# Adafruit_AHT20_Temperature_Humidity.net
KiCad netlist of a schematic drawn in EAGLE
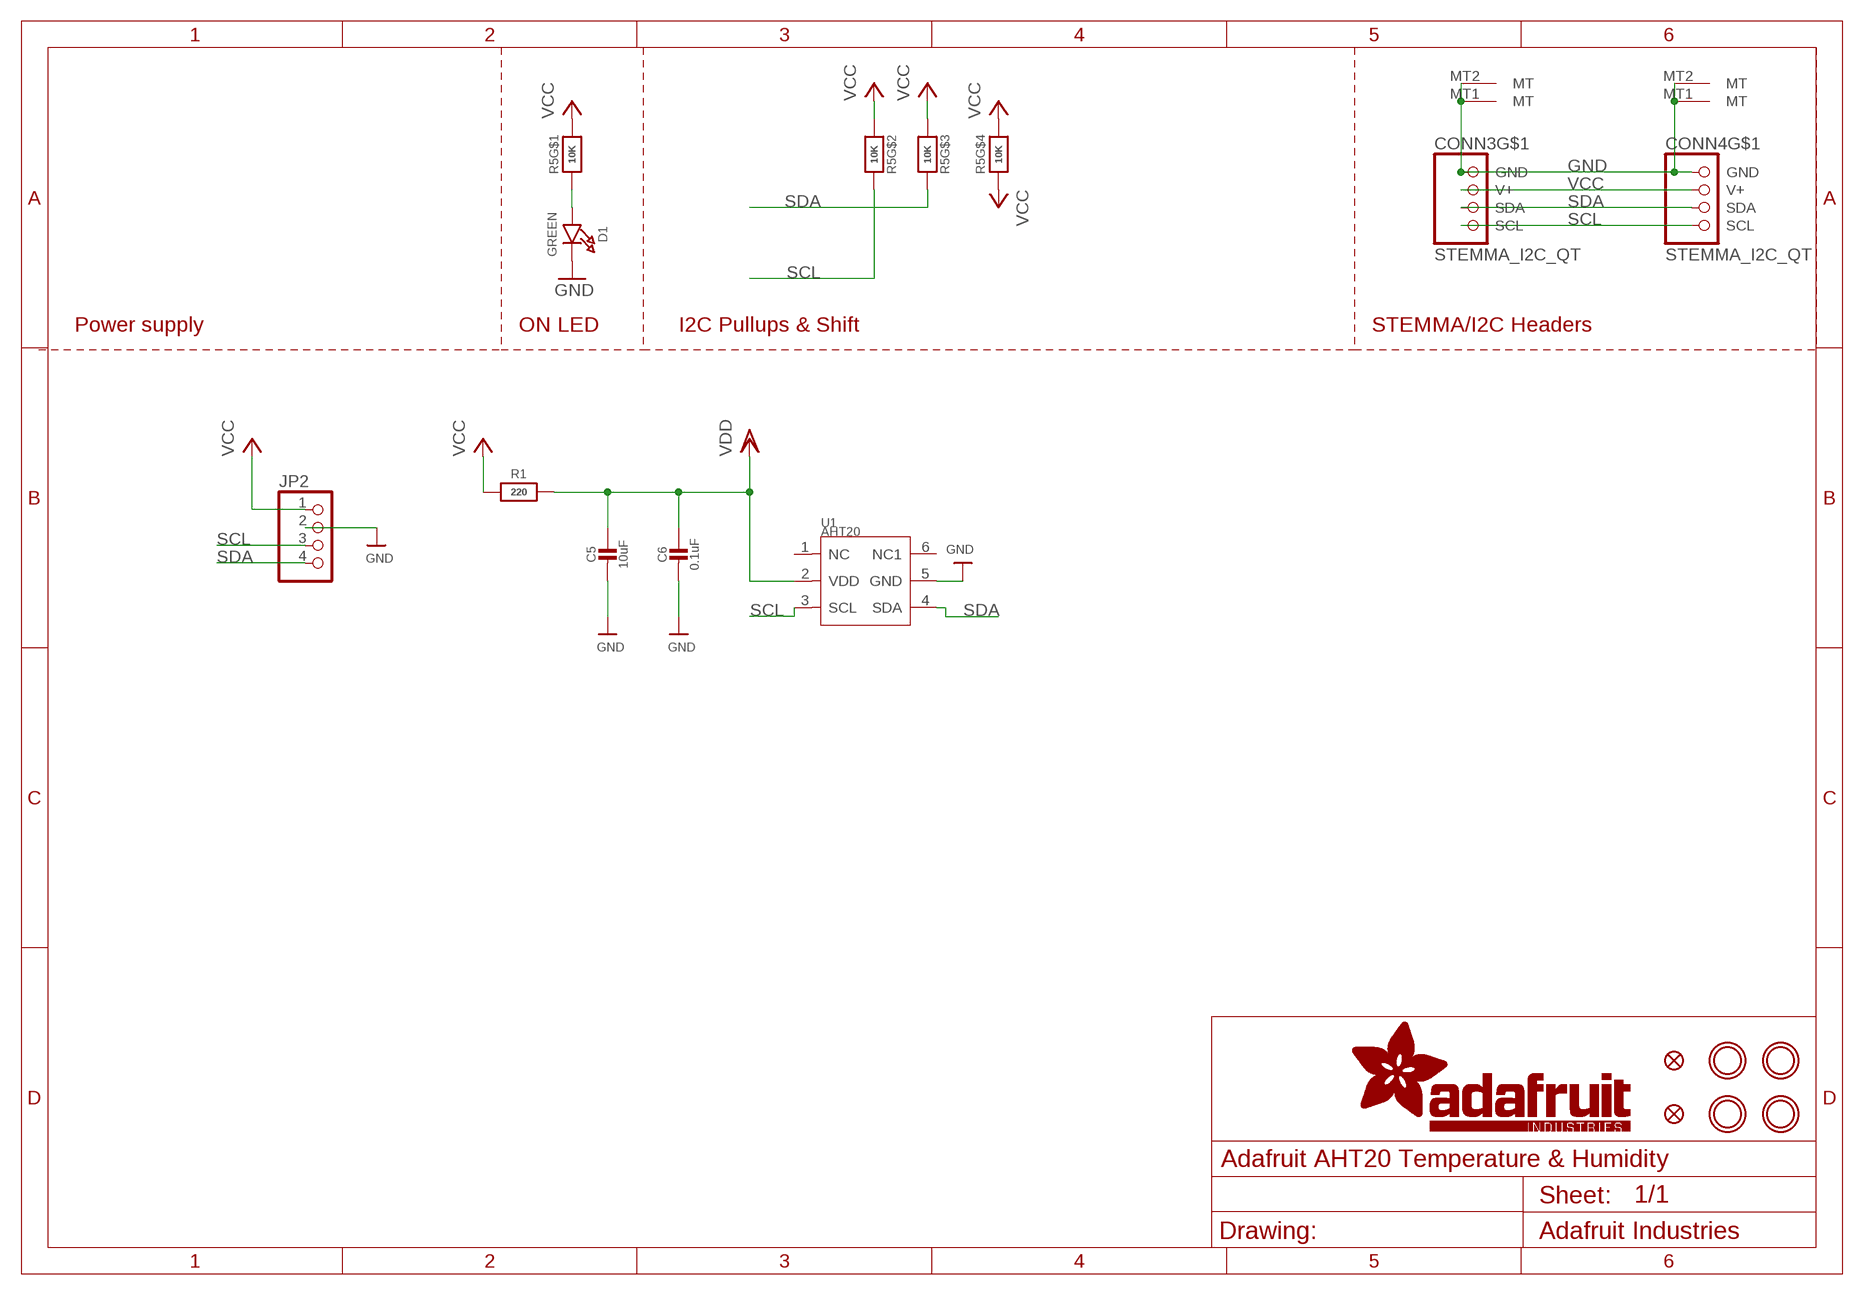
[diagram p0: schematic, sheet 1]

(export (version "E")
  (design (tool "Eeschema 10.0.6"))
  (components
    (comp (ref "C5")
      (value "10uF")
      (footprint "eagle-import:0805-NO")
      (libsource (lib "eagle-import") (part "CAP_CERAMIC0805-NOOUTLINE"))
    )
    (comp (ref "C6")
      (value "0.1uF")
      (footprint "eagle-import:0603-NO")
      (libsource (lib "eagle-import") (part "CAP_CERAMIC0603_NO"))
    )
    (comp (ref "CONN3")
      (value "STEMMA_I2C_QT")
      (footprint "eagle-import:JST_SH4")
      (libsource (lib "eagle-import") (part "STEMMA_I2C_QT"))
    )
    (comp (ref "CONN4")
      (value "STEMMA_I2C_QT")
      (footprint "eagle-import:JST_SH4")
      (libsource (lib "eagle-import") (part "STEMMA_I2C_QT"))
    )
    (comp (ref "D1")
      (value "GREEN")
      (footprint "eagle-import:CHIPLED_0603_NOOUTLINE")
      (libsource (lib "eagle-import") (part "LED0603_NOOUTLINE"))
    )
    (comp (ref "FID3")
      (value "FIDUCIAL_1MM")
      (footprint "eagle-import:FIDUCIAL_1MM")
      (libsource (lib "eagle-import") (part "FIDUCIAL_1MM"))
    )
    (comp (ref "FID4")
      (value "FIDUCIAL_1MM")
      (footprint "eagle-import:FIDUCIAL_1MM")
      (libsource (lib "eagle-import") (part "FIDUCIAL_1MM"))
    )
    (comp (ref "JP2")
      (value "HEADER-1X476MIL")
      (footprint "eagle-import:1X04_ROUND_76")
      (libsource (lib "eagle-import") (part "HEADER-1X476MIL"))
    )
    (comp (ref "R1")
      (value "220")
      (footprint "eagle-import:0603-NO")
      (libsource (lib "eagle-import") (part "RESISTOR_0603_NOOUT"))
    )
    (comp (ref "R5")
      (value "10K")
      (footprint "eagle-import:RESPACK_4X0603")
      (libsource (lib "eagle-import") (part "RESISTOR_4PACK"))
    )
    (comp (ref "U$19")
      (value "MOUNTINGHOLE2.5")
      (footprint "eagle-import:MOUNTINGHOLE_2.5_PLATED")
      (libsource (lib "eagle-import") (part "MOUNTINGHOLE2.5"))
    )
    (comp (ref "U$20")
      (value "MOUNTINGHOLE2.5")
      (footprint "eagle-import:MOUNTINGHOLE_2.5_PLATED")
      (libsource (lib "eagle-import") (part "MOUNTINGHOLE2.5"))
    )
    (comp (ref "U$22")
      (value "MOUNTINGHOLE2.5")
      (footprint "eagle-import:MOUNTINGHOLE_2.5_PLATED")
      (libsource (lib "eagle-import") (part "MOUNTINGHOLE2.5"))
    )
    (comp (ref "U$25")
      (value "MOUNTINGHOLE2.5")
      (footprint "eagle-import:MOUNTINGHOLE_2.5_PLATED")
      (libsource (lib "eagle-import") (part "MOUNTINGHOLE2.5"))
    )
    (comp (ref "U1")
      (value "AHT20")
      (footprint "eagle-import:SNR6-1.0-3X3X1MM")
      (libsource (lib "eagle-import") (part "SENSOR-AHT20"))
    )
  )
  (nets
    (net (code "1") (name "/SCL") (class "Default")
      (node (ref "CONN3") (pin "4") (pinfunction "SCL_4") (pintype "passive"))
      (node (ref "CONN4") (pin "4") (pinfunction "SCL_4") (pintype "passive"))
      (node (ref "JP2") (pin "3") (pinfunction "3_3") (pintype "passive"))
      (node (ref "R5") (pin "7") (pinfunction "2_7") (pintype "passive"))
      (node (ref "U1") (pin "3") (pinfunction "SCL_3") (pintype "bidirectional"))
    )
    (net (code "2") (name "/SDA") (class "Default")
      (node (ref "CONN3") (pin "3") (pinfunction "SDA_3") (pintype "passive"))
      (node (ref "CONN4") (pin "3") (pinfunction "SDA_3") (pintype "passive"))
      (node (ref "JP2") (pin "4") (pinfunction "4_4") (pintype "passive"))
      (node (ref "R5") (pin "6") (pinfunction "2_6") (pintype "passive"))
      (node (ref "U1") (pin "4") (pinfunction "SDA_4") (pintype "bidirectional"))
    )
    (net (code "3") (name "GND") (class "Default")
      (node (ref "C5") (pin "2") (pinfunction "2_2") (pintype "passive"))
      (node (ref "C6") (pin "2") (pinfunction "2_2") (pintype "passive"))
      (node (ref "CONN3") (pin "1") (pinfunction "GND_1") (pintype "passive"))
      (node (ref "CONN3") (pin "MT1") (pinfunction "MT_MT1") (pintype "bidirectional"))
      (node (ref "CONN3") (pin "MT2") (pinfunction "MT_MT2") (pintype "bidirectional"))
      (node (ref "CONN4") (pin "1") (pinfunction "GND_1") (pintype "passive"))
      (node (ref "CONN4") (pin "MT1") (pinfunction "MT_MT1") (pintype "bidirectional"))
      (node (ref "CONN4") (pin "MT2") (pinfunction "MT_MT2") (pintype "bidirectional"))
      (node (ref "D1") (pin "C") (pinfunction "C_C") (pintype "passive"))
      (node (ref "JP2") (pin "2") (pinfunction "2_2") (pintype "passive"))
      (node (ref "U1") (pin "5") (pinfunction "GND_5") (pintype "bidirectional"))
    )
    (net (code "4") (name "Net-(D1-PadA)") (class "Default")
      (node (ref "D1") (pin "A") (pinfunction "A_A") (pintype "passive"))
      (node (ref "R5") (pin "1") (pinfunction "1_1") (pintype "passive"))
    )
    (net (code "5") (name "VCC") (class "Default")
      (node (ref "CONN3") (pin "2") (pinfunction "V+_2") (pintype "passive"))
      (node (ref "CONN4") (pin "2") (pinfunction "V+_2") (pintype "passive"))
      (node (ref "JP2") (pin "1") (pinfunction "1_1") (pintype "passive"))
      (node (ref "R1") (pin "1") (pinfunction "1_1") (pintype "passive"))
      (node (ref "R5") (pin "2") (pinfunction "1_2") (pintype "passive"))
      (node (ref "R5") (pin "3") (pinfunction "1_3") (pintype "passive"))
      (node (ref "R5") (pin "4") (pinfunction "1_4") (pintype "passive"))
      (node (ref "R5") (pin "5") (pinfunction "2_5") (pintype "passive"))
      (node (ref "R5") (pin "8") (pinfunction "2_8") (pintype "passive"))
    )
    (net (code "6") (name "VDD") (class "Default")
      (node (ref "C5") (pin "1") (pinfunction "1_1") (pintype "passive"))
      (node (ref "C6") (pin "1") (pinfunction "1_1") (pintype "passive"))
      (node (ref "R1") (pin "2") (pinfunction "2_2") (pintype "passive"))
      (node (ref "U1") (pin "2") (pinfunction "VDD_2") (pintype "bidirectional"))
    )
    (net (code "7") (name "unconnected-(U1-NC-Pad1)") (class "Default")
      (node (ref "U1") (pin "1") (pinfunction "NC_1") (pintype "bidirectional"))
    )
    (net (code "8") (name "unconnected-(U1-NC1-Pad6)") (class "Default")
      (node (ref "U1") (pin "6") (pinfunction "NC1_6") (pintype "bidirectional"))
    )
  )
)
